# Robot_v4.net
KiCad netlist of a schematic drawn in EAGLE
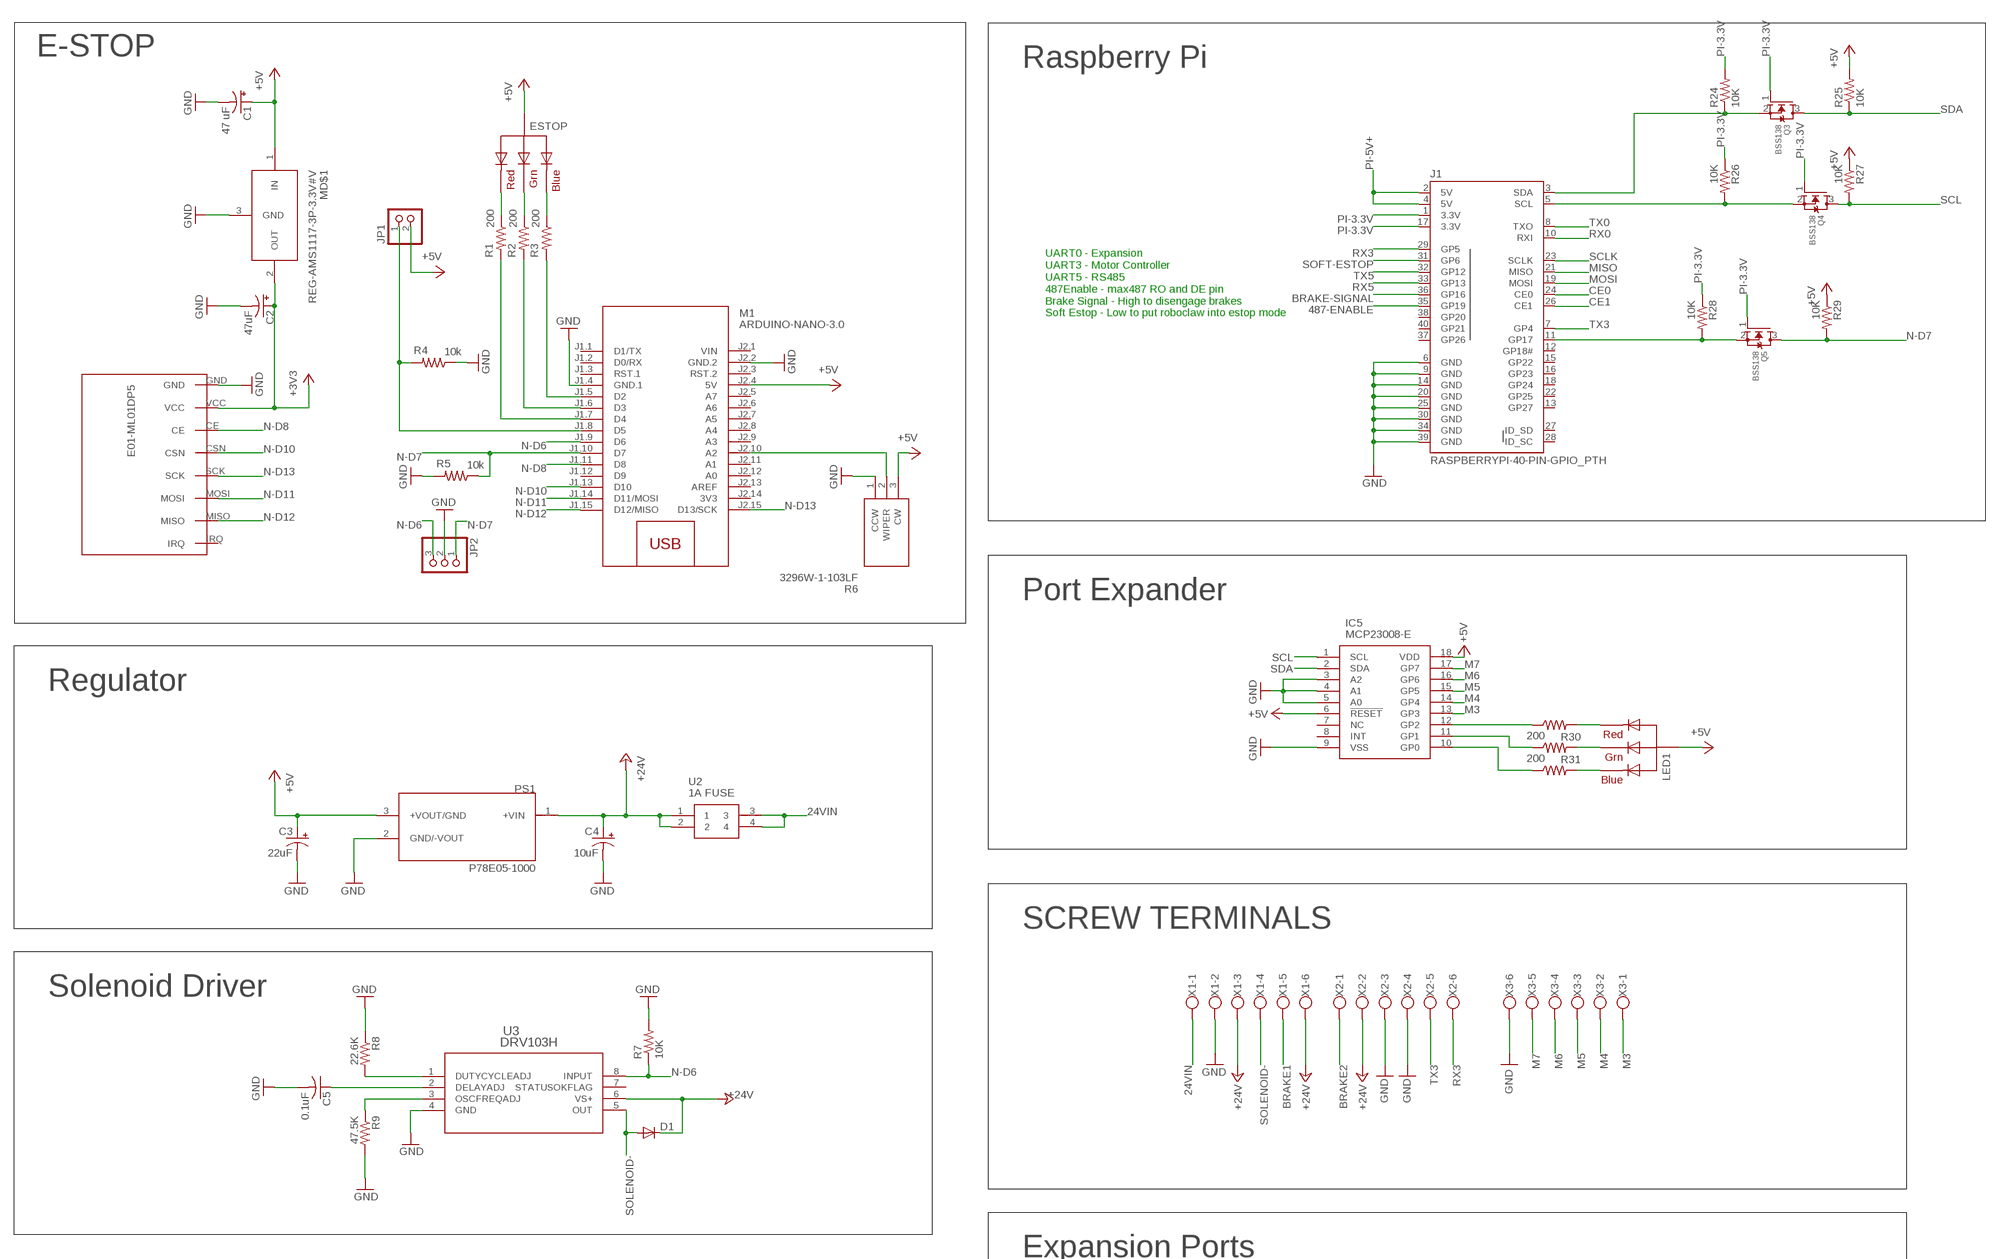
[diagram p0: schematic, sheet 1, part 1 of 2]
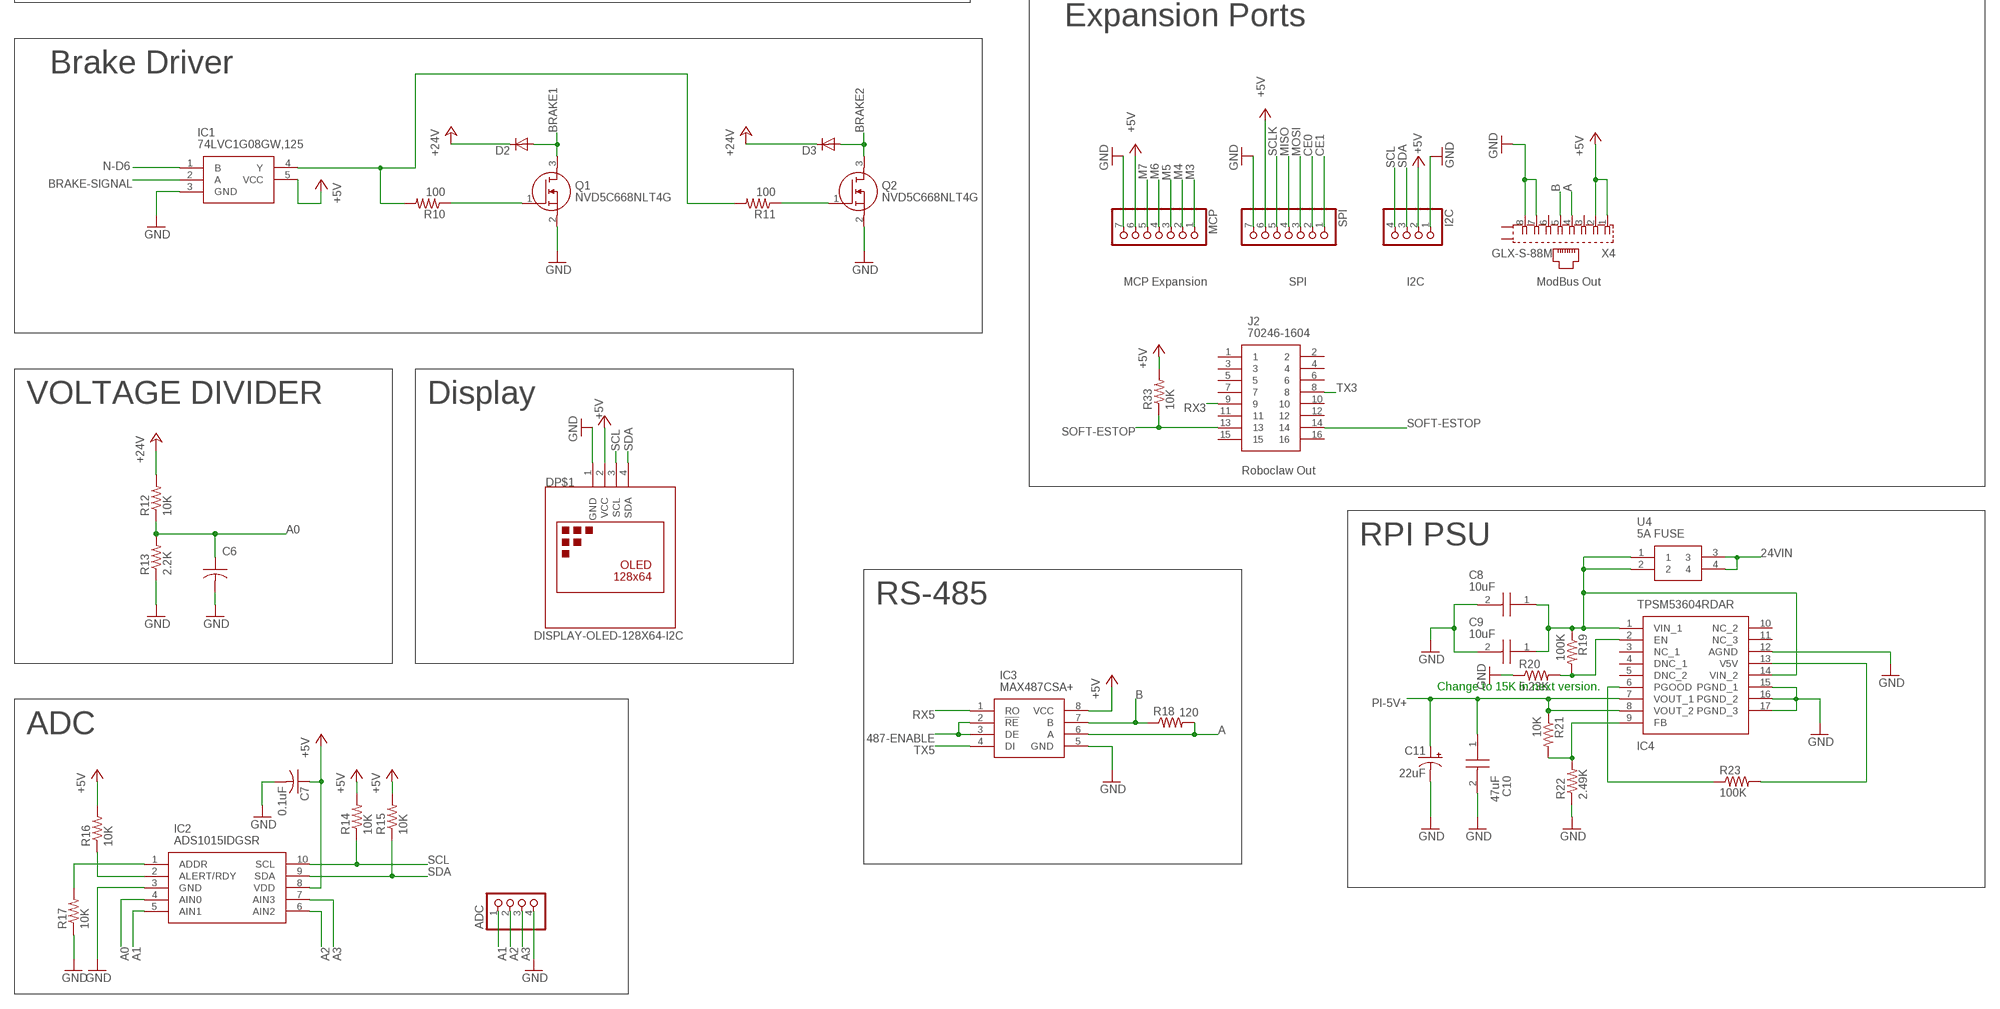
[diagram p1: schematic, sheet 1, part 2 of 2]

(export (version "E")
  (design (tool "Eeschema 10.0.6"))
  (components
    (comp (ref "ADC")
      (value "PINHD-1X4")
      (footprint "eagle-import:1X04")
      (libsource (lib "eagle-import") (part "PINHD-1X4"))
    )
    (comp (ref "C1")
      (value "47 uF")
      (footprint "eagle-import:E2,5-5")
      (libsource (lib "eagle-import") (part "CPOL-USE2.5-5"))
    )
    (comp (ref "C2")
      (value "47uF")
      (footprint "eagle-import:E2,5-5")
      (libsource (lib "eagle-import") (part "CPOL-USE2.5-5"))
    )
    (comp (ref "C3")
      (value "22uF")
      (footprint "eagle-import:E3,5-8")
      (libsource (lib "eagle-import") (part "CPOL-USE3.5-8"))
    )
    (comp (ref "C4")
      (value "10uF")
      (footprint "eagle-import:E3,5-8")
      (libsource (lib "eagle-import") (part "CPOL-USE3.5-8"))
    )
    (comp (ref "C5")
      (value "0.1uF")
      (footprint "eagle-import:C0805")
      (libsource (lib "eagle-import") (part "C-USC0805"))
    )
    (comp (ref "C6")
      (value "0.01uF")
      (footprint "eagle-import:C0805")
      (libsource (lib "eagle-import") (part "C-USC0805"))
    )
    (comp (ref "C7")
      (value "0.1uF")
      (footprint "eagle-import:C0805")
      (libsource (lib "eagle-import") (part "C-USC0805"))
    )
    (comp (ref "C8")
      (value "10uF")
      (footprint "eagle-import:CAPC3216X180N")
      (fields
        (field (name "MANUFACTURER_PART_NUMBER") "GRT31CR61H106ME01L")
        (field (name "MOUSER_PART_NUMBER") "81-GRT31CR61H106ME1L")
      )
      (libsource (lib "eagle-import") (part "GRT31CR61H106ME01L"))
    )
    (comp (ref "C9")
      (value "10uF")
      (footprint "eagle-import:CAPC3216X180N")
      (fields
        (field (name "MANUFACTURER_PART_NUMBER") "GRT31CR61H106ME01L")
        (field (name "MOUSER_PART_NUMBER") "81-GRT31CR61H106ME1L")
      )
      (libsource (lib "eagle-import") (part "GRT31CR61H106ME01L"))
    )
    (comp (ref "C10")
      (value "47uF")
      (footprint "eagle-import:CAPC2012X145N")
      (fields
        (field (name "MANUFACTURER_PART_NUMBER") "GRM21BR61A476ME15L")
        (field (name "MOUSER_PART_NUMBER") "81-GRM21BR61A476ME5L")
      )
      (libsource (lib "eagle-import") (part "GRM21BR61A476ME15L"))
    )
    (comp (ref "C11")
      (value "22uF")
      (footprint "eagle-import:E3,5-8")
      (libsource (lib "eagle-import") (part "CPOL-USE3.5-8"))
    )
    (comp (ref "D1")
      (value "DIODESOD-123")
      (footprint "eagle-import:SOD-123")
      (libsource (lib "eagle-import") (part "DIODESOD-123"))
    )
    (comp (ref "D2")
      (value "DIODESOD-123")
      (footprint "eagle-import:SOD-123")
      (libsource (lib "eagle-import") (part "DIODESOD-123"))
    )
    (comp (ref "D3")
      (value "DIODESOD-123")
      (footprint "eagle-import:SOD-123")
      (libsource (lib "eagle-import") (part "DIODESOD-123"))
    )
    (comp (ref "DP$1")
      (value "DISPLAY-OLED-128X64-I2C")
      (footprint "eagle-import:DISPLAY-OLED-128X64-I2C")
      (libsource (lib "eagle-import") (part "DISPLAY-OLED-128X64-I2C"))
    )
    (comp (ref "ESTOP")
      (value "RGBLED_CA-5MM")
      (footprint "eagle-import:LED5MMRGB")
      (libsource (lib "eagle-import") (part "RGBLED_CA-5MM"))
    )
    (comp (ref "I2C")
      (value "PINHD-1X4")
      (footprint "eagle-import:1X04")
      (libsource (lib "eagle-import") (part "PINHD-1X4"))
    )
    (comp (ref "IC1")
      (value "74LVC1G08GW,125")
      (footprint "eagle-import:SOT65P212X110-5N")
      (fields (field (name "MOUSER_PART_NUMBER") "771-74LVC1G08GW-G"))
      (libsource (lib "eagle-import") (part "74LVC1G08GW,125"))
    )
    (comp (ref "IC2")
      (value "ADS1015IDGSR")
      (footprint "eagle-import:SOP50P490X110-10N")
      (fields (field (name "MOUSER_PART_NUMBER") "595-ADS1015IDGSR"))
      (libsource (lib "eagle-import") (part "ADS1015IDGSR"))
    )
    (comp (ref "IC3")
      (value "MAX487CSA+")
      (footprint "eagle-import:SOIC127P600X175-8N")
      (fields (field (name "MOUSER_PART_NUMBER") "700-MAX487CSA"))
      (libsource (lib "eagle-import") (part "MAX487CSA+"))
    )
    (comp (ref "IC4")
      (value "TPSM53604RDAR")
      (footprint "eagle-import:TPSM53604RDAR")
      (fields (field (name "MOUSER_PART_NUMBER") "595-TPSM53604RDAR"))
      (libsource (lib "eagle-import") (part "TPSM53604RDAR"))
    )
    (comp (ref "IC5")
      (value "MCP23008-E")
      (footprint "eagle-import:SOIC127P1030X265-18N")
      (fields
        (field (name "MANUFACTURER_PART_NUMBER") "MCP23008-E/SO")
        (field (name "MOUSER_PART_NUMBER") "579-MCP23008-E/SO")
      )
      (libsource (lib "eagle-import") (part "MCP23008-E_SO"))
    )
    (comp (ref "J1")
      (value "RASPBERRYPI-40-PIN-GPIO_PTH")
      (footprint "eagle-import:2X20_SHROUDED")
      (libsource (lib "eagle-import") (part "RASPBERRYPI-40-PIN-GPIO_PTH"))
    )
    (comp (ref "J2")
      (value "70246-1604")
      (footprint "eagle-import:SHDR16W64P254_2X8_2794X889X947")
      (fields (field (name "MOUSER_PART_NUMBER") "538-70246-1604"))
      (libsource (lib "eagle-import") (part "70246-1604"))
    )
    (comp (ref "JP1")
      (value "PINHD-1X2")
      (footprint "eagle-import:1X02")
      (libsource (lib "eagle-import") (part "PINHD-1X2"))
    )
    (comp (ref "JP2")
      (value "PINHD-1X3")
      (footprint "eagle-import:1X03")
      (libsource (lib "eagle-import") (part "PINHD-1X3"))
    )
    (comp (ref "LED1")
      (value "RGBLED_CA-5MM")
      (footprint "eagle-import:LED5MMRGB")
      (libsource (lib "eagle-import") (part "RGBLED_CA-5MM"))
    )
    (comp (ref "M1")
      (value "ARDUINO-NANO-3.0")
      (footprint "eagle-import:ARDUINO-NANO-3.0")
      (libsource (lib "eagle-import") (part "ARDUINO-NANO-3.0"))
    )
    (comp (ref "MCP")
      (value "PINHD-1X7")
      (footprint "eagle-import:1X07")
      (libsource (lib "eagle-import") (part "PINHD-1X7"))
    )
    (comp (ref "MD$1")
      (value "REG-AMS1117-3P-3.3V#V")
      (footprint "eagle-import:REG-AMS1117-3P#V")
      (libsource (lib "eagle-import") (part "REG-AMS1117-3P-#V3.3V"))
    )
    (comp (ref "MD$2")
      (value "E01-ML01DP5")
      (footprint "eagle-import:E01-ML01DP5")
      (libsource (lib "eagle-import") (part "E01-ML01DP5"))
    )
    (comp (ref "PS1")
      (value "P78E05-1000")
      (footprint "eagle-import:CONV_P78E05-1000")
      (fields (field (name "MANUFACTURER") "CUI Inc"))
      (libsource (lib "eagle-import") (part "P78E05-1000"))
    )
    (comp (ref "Q1")
      (value "NVD5C668NLT4G")
      (footprint "eagle-import:DPAK_(SINGLE-GAUGE)_TO-252(369")
      (fields (field (name "MOUSER_PART_NUMBER") "863-NVD5C668NLT4G"))
      (libsource (lib "eagle-import") (part "NVD5C668NLT4G"))
    )
    (comp (ref "Q2")
      (value "NVD5C668NLT4G")
      (footprint "eagle-import:DPAK_(SINGLE-GAUGE)_TO-252(369")
      (fields (field (name "MOUSER_PART_NUMBER") "863-NVD5C668NLT4G"))
      (libsource (lib "eagle-import") (part "NVD5C668NLT4G"))
    )
    (comp (ref "Q3")
      (value "BSS138")
      (footprint "eagle-import:SOT23")
      (libsource (lib "eagle-import") (part "MOSFET-NREFLOW"))
    )
    (comp (ref "Q4")
      (value "BSS138")
      (footprint "eagle-import:SOT23")
      (libsource (lib "eagle-import") (part "MOSFET-NREFLOW"))
    )
    (comp (ref "Q5")
      (value "BSS138")
      (footprint "eagle-import:SOT23")
      (libsource (lib "eagle-import") (part "MOSFET-NREFLOW"))
    )
    (comp (ref "R1")
      (value "200")
      (footprint "eagle-import:M0805")
      (libsource (lib "eagle-import") (part "R-US_M0805"))
    )
    (comp (ref "R2")
      (value "200")
      (footprint "eagle-import:M0805")
      (libsource (lib "eagle-import") (part "R-US_M0805"))
    )
    (comp (ref "R3")
      (value "200")
      (footprint "eagle-import:M0805")
      (libsource (lib "eagle-import") (part "R-US_M0805"))
    )
    (comp (ref "R4")
      (value "10k")
      (footprint "eagle-import:M0805")
      (libsource (lib "eagle-import") (part "R-US_M0805"))
    )
    (comp (ref "R5")
      (value "10k")
      (footprint "eagle-import:M0805")
      (libsource (lib "eagle-import") (part "R-US_M0805"))
    )
    (comp (ref "R6")
      (value "3296W-1-103LF")
      (footprint "eagle-import:SHDR3W54P0X254_1X3_953X483X115")
      (fields (field (name "MOUSER_PART_NUMBER") "652-3296W-1-103LF"))
      (libsource (lib "eagle-import") (part "3296W-1-103LF"))
    )
    (comp (ref "R7")
      (value "10K")
      (footprint "eagle-import:M0805")
      (libsource (lib "eagle-import") (part "R-US_M0805"))
    )
    (comp (ref "R8")
      (value "22.6K")
      (footprint "eagle-import:M0805")
      (libsource (lib "eagle-import") (part "R-US_M0805"))
    )
    (comp (ref "R9")
      (value "47.5K")
      (footprint "eagle-import:M0805")
      (libsource (lib "eagle-import") (part "R-US_M0805"))
    )
    (comp (ref "R10")
      (value "100")
      (footprint "eagle-import:M0805")
      (libsource (lib "eagle-import") (part "R-US_M0805"))
    )
    (comp (ref "R11")
      (value "100")
      (footprint "eagle-import:M0805")
      (libsource (lib "eagle-import") (part "R-US_M0805"))
    )
    (comp (ref "R12")
      (value "10K")
      (footprint "eagle-import:M0805")
      (libsource (lib "eagle-import") (part "R-US_M0805"))
    )
    (comp (ref "R13")
      (value "2.2K")
      (footprint "eagle-import:M0805")
      (libsource (lib "eagle-import") (part "R-US_M0805"))
    )
    (comp (ref "R14")
      (value "10K")
      (footprint "eagle-import:R0805")
      (libsource (lib "eagle-import") (part "R-US_R0805"))
    )
    (comp (ref "R15")
      (value "10K")
      (footprint "eagle-import:R0805")
      (libsource (lib "eagle-import") (part "R-US_R0805"))
    )
    (comp (ref "R16")
      (value "10K")
      (footprint "eagle-import:R0805")
      (libsource (lib "eagle-import") (part "R-US_R0805"))
    )
    (comp (ref "R17")
      (value "10K")
      (footprint "eagle-import:R0805")
      (libsource (lib "eagle-import") (part "R-US_R0805"))
    )
    (comp (ref "R18")
      (value "120")
      (footprint "eagle-import:R0805")
      (libsource (lib "eagle-import") (part "R-US_R0805"))
    )
    (comp (ref "R19")
      (value "100K")
      (footprint "eagle-import:R0805")
      (libsource (lib "eagle-import") (part "R-US_R0805"))
    )
    (comp (ref "R20")
      (value "5.23K")
      (footprint "eagle-import:R0805")
      (libsource (lib "eagle-import") (part "R-US_R0805"))
    )
    (comp (ref "R21")
      (value "10K")
      (footprint "eagle-import:R0805")
      (libsource (lib "eagle-import") (part "R-US_R0805"))
    )
    (comp (ref "R22")
      (value "2.49K")
      (footprint "eagle-import:R0805")
      (libsource (lib "eagle-import") (part "R-US_R0805"))
    )
    (comp (ref "R23")
      (value "100K")
      (footprint "eagle-import:R0805")
      (libsource (lib "eagle-import") (part "R-US_R0805"))
    )
    (comp (ref "R24")
      (value "10K")
      (footprint "eagle-import:R0805")
      (libsource (lib "eagle-import") (part "R-US_R0805"))
    )
    (comp (ref "R25")
      (value "10K")
      (footprint "eagle-import:R0805")
      (libsource (lib "eagle-import") (part "R-US_R0805"))
    )
    (comp (ref "R26")
      (value "10K")
      (footprint "eagle-import:R0805")
      (libsource (lib "eagle-import") (part "R-US_R0805"))
    )
    (comp (ref "R27")
      (value "10K")
      (footprint "eagle-import:R0805")
      (libsource (lib "eagle-import") (part "R-US_R0805"))
    )
    (comp (ref "R28")
      (value "10K")
      (footprint "eagle-import:R0805")
      (libsource (lib "eagle-import") (part "R-US_R0805"))
    )
    (comp (ref "R29")
      (value "10K")
      (footprint "eagle-import:R0805")
      (libsource (lib "eagle-import") (part "R-US_R0805"))
    )
    (comp (ref "R30")
      (value "200")
      (footprint "eagle-import:M0805")
      (libsource (lib "eagle-import") (part "R-US_M0805"))
    )
    (comp (ref "R31")
      (value "200")
      (footprint "eagle-import:M0805")
      (libsource (lib "eagle-import") (part "R-US_M0805"))
    )
    (comp (ref "R32")
      (value "200")
      (footprint "eagle-import:M0805")
      (libsource (lib "eagle-import") (part "R-US_M0805"))
    )
    (comp (ref "R33")
      (value "10K")
      (footprint "eagle-import:R0805")
      (libsource (lib "eagle-import") (part "R-US_R0805"))
    )
    (comp (ref "SPI")
      (value "PINHD-1X7")
      (footprint "eagle-import:1X07")
      (libsource (lib "eagle-import") (part "PINHD-1X7"))
    )
    (comp (ref "U2")
      (value "1A FUSE")
      (footprint "eagle-import:3568")
      (fields (field (name "MANUFACTURER_PART_NUMBER") "3568") (field (name "MOUSER_PART_NUMBER") "534-3568"))
      (libsource (lib "eagle-import") (part "3568"))
    )
    (comp (ref "U3")
      (value "DRV103H")
      (footprint "eagle-import:DDA8")
      (libsource (lib "eagle-import") (part "DRV103H"))
    )
    (comp (ref "U4")
      (value "5A FUSE")
      (footprint "eagle-import:3568")
      (fields (field (name "MANUFACTURER_PART_NUMBER") "3568") (field (name "MOUSER_PART_NUMBER") "534-3568"))
      (libsource (lib "eagle-import") (part "3568"))
    )
    (comp (ref "X1")
      (value "W237-136")
      (footprint "eagle-import:W237-136")
      (fields (field (name "MPN") "237-136"))
      (libsource (lib "eagle-import") (part "W237-136"))
    )
    (comp (ref "X2")
      (value "W237-136")
      (footprint "eagle-import:W237-136")
      (fields (field (name "MPN") "237-136"))
      (libsource (lib "eagle-import") (part "W237-136"))
    )
    (comp (ref "X3")
      (value "W237-136")
      (footprint "eagle-import:W237-136")
      (fields (field (name "MPN") "237-136"))
      (libsource (lib "eagle-import") (part "W237-136"))
    )
    (comp (ref "X4")
      (value "GLX-S-88M")
      (footprint "eagle-import:GLX-S-88M")
      (libsource (lib "eagle-import") (part "GLX-S-88M"))
    )
  )
  (nets
    (net (code "1") (name "+3V3") (class "Default")
      (node (ref "C2") (pin "+") (pinfunction "+_+") (pintype "passive"))
      (node (ref "MD$1") (pin "2") (pinfunction "OUT_2") (pintype "bidirectional"))
      (node (ref "MD$2") (pin "VCC") (pinfunction "VCC_VCC") (pintype "bidirectional"))
    )
    (net (code "2") (name "+5V") (class "Default")
      (node (ref "C1") (pin "+") (pinfunction "+_+") (pintype "passive"))
      (node (ref "C3") (pin "+") (pinfunction "+_+") (pintype "passive"))
      (node (ref "C7") (pin "1") (pinfunction "1_1") (pintype "passive"))
      (node (ref "DP$1") (pin "2") (pinfunction "VCC_2") (pintype "power_in"))
      (node (ref "ESTOP") (pin "2") (pinfunction "VCC_2") (pintype "bidirectional"))
      (node (ref "I2C") (pin "2") (pinfunction "2_2") (pintype "passive"))
      (node (ref "IC1") (pin "5") (pinfunction "VCC_5") (pintype "power_in"))
      (node (ref "IC2") (pin "8") (pinfunction "VDD_8") (pintype "bidirectional"))
      (node (ref "IC3") (pin "8") (pinfunction "VCC_8") (pintype "power_in"))
      (node (ref "IC5") (pin "18") (pinfunction "VDD_18") (pintype "power_in"))
      (node (ref "IC5") (pin "6") (pinfunction "~{RESET}_6") (pintype "bidirectional"))
      (node (ref "JP1") (pin "2") (pinfunction "2_2") (pintype "passive"))
      (node (ref "LED1") (pin "2") (pinfunction "VCC_2") (pintype "bidirectional"))
      (node (ref "M1") (pin "J2.4") (pinfunction "5V_J2.4") (pintype "power_in"))
      (node (ref "MCP") (pin "6") (pinfunction "6_6") (pintype "passive"))
      (node (ref "MD$1") (pin "1") (pinfunction "IN_1") (pintype "bidirectional"))
      (node (ref "PS1") (pin "3") (pinfunction "+VOUT/GND_3") (pintype "power_in"))
      (node (ref "R14") (pin "2") (pinfunction "2_2") (pintype "passive"))
      (node (ref "R15") (pin "2") (pinfunction "2_2") (pintype "passive"))
      (node (ref "R16") (pin "2") (pinfunction "2_2") (pintype "passive"))
      (node (ref "R25") (pin "2") (pinfunction "2_2") (pintype "passive"))
      (node (ref "R27") (pin "1") (pinfunction "1_1") (pintype "passive"))
      (node (ref "R29") (pin "1") (pinfunction "1_1") (pintype "passive"))
      (node (ref "R33") (pin "2") (pinfunction "2_2") (pintype "passive"))
      (node (ref "R6") (pin "3") (pinfunction "CW_3") (pintype "bidirectional"))
      (node (ref "SPI") (pin "6") (pinfunction "6_6") (pintype "passive"))
      (node (ref "X4") (pin "1") (pinfunction "1_1") (pintype "passive"))
      (node (ref "X4") (pin "2") (pinfunction "2_2") (pintype "passive"))
    )
    (net (code "3") (name "+24V") (class "Default")
      (node (ref "C4") (pin "+") (pinfunction "+_+") (pintype "passive"))
      (node (ref "D1") (pin "C") (pinfunction "C_C") (pintype "passive"))
      (node (ref "D2") (pin "C") (pinfunction "C_C") (pintype "passive"))
      (node (ref "D3") (pin "C") (pinfunction "C_C") (pintype "passive"))
      (node (ref "PS1") (pin "1") (pinfunction "+VIN_1") (pintype "input"))
      (node (ref "R12") (pin "2") (pinfunction "2_2") (pintype "passive"))
      (node (ref "U2") (pin "1") (pinfunction "1_1") (pintype "bidirectional"))
      (node (ref "U2") (pin "2") (pinfunction "2_2") (pintype "bidirectional"))
      (node (ref "U3") (pin "6") (pinfunction "VS+_6") (pintype "power_in"))
      (node (ref "X1") (pin "3") (pinfunction "KL_3") (pintype "passive"))
      (node (ref "X1") (pin "6") (pinfunction "KL_6") (pintype "passive"))
      (node (ref "X2") (pin "2") (pinfunction "KL_2") (pintype "passive"))
    )
    (net (code "4") (name "/3V3") (class "Default")
      (node (ref "M1") (pin "J2.14") (pinfunction "3V3_J2.14") (pintype "power_in"))
    )
    (net (code "5") (name "/24VIN") (class "Default")
      (node (ref "U2") (pin "3") (pinfunction "3_3") (pintype "bidirectional"))
      (node (ref "U2") (pin "4") (pinfunction "4_4") (pintype "bidirectional"))
      (node (ref "U4") (pin "3") (pinfunction "3_3") (pintype "bidirectional"))
      (node (ref "U4") (pin "4") (pinfunction "4_4") (pintype "bidirectional"))
      (node (ref "X1") (pin "1") (pinfunction "KL_1") (pintype "passive"))
    )
    (net (code "6") (name "/487-ENABLE") (class "Default")
      (node (ref "IC3") (pin "2") (pinfunction "~{RE}_2") (pintype "bidirectional"))
      (node (ref "IC3") (pin "3") (pinfunction "DE_3") (pintype "bidirectional"))
      (node (ref "J1") (pin "35") (pinfunction "GP19_35") (pintype "bidirectional"))
    )
    (net (code "7") (name "/A") (class "Default")
      (node (ref "IC3") (pin "6") (pinfunction "A_6") (pintype "bidirectional"))
      (node (ref "R18") (pin "2") (pinfunction "2_2") (pintype "passive"))
      (node (ref "X4") (pin "4") (pinfunction "4_4") (pintype "passive"))
    )
    (net (code "8") (name "/A0") (class "Default")
      (node (ref "C6") (pin "1") (pinfunction "1_1") (pintype "passive"))
      (node (ref "IC2") (pin "4") (pinfunction "AIN0_4") (pintype "bidirectional"))
      (node (ref "R12") (pin "1") (pinfunction "1_1") (pintype "passive"))
      (node (ref "R13") (pin "2") (pinfunction "2_2") (pintype "passive"))
    )
    (net (code "9") (name "/A1") (class "Default")
      (node (ref "ADC") (pin "1") (pinfunction "1_1") (pintype "passive"))
      (node (ref "IC2") (pin "5") (pinfunction "AIN1_5") (pintype "bidirectional"))
    )
    (net (code "10") (name "/A2") (class "Default")
      (node (ref "ADC") (pin "2") (pinfunction "2_2") (pintype "passive"))
      (node (ref "IC2") (pin "6") (pinfunction "AIN2_6") (pintype "bidirectional"))
    )
    (net (code "11") (name "/A3") (class "Default")
      (node (ref "ADC") (pin "3") (pinfunction "3_3") (pintype "passive"))
      (node (ref "IC2") (pin "7") (pinfunction "AIN3_7") (pintype "bidirectional"))
    )
    (net (code "12") (name "/B") (class "Default")
      (node (ref "IC3") (pin "7") (pinfunction "B_7") (pintype "bidirectional"))
      (node (ref "R18") (pin "1") (pinfunction "1_1") (pintype "passive"))
      (node (ref "X4") (pin "5") (pinfunction "5_5") (pintype "passive"))
    )
    (net (code "13") (name "/BRAKE-SIGNAL") (class "Default")
      (node (ref "IC1") (pin "2") (pinfunction "A_2") (pintype "bidirectional"))
      (node (ref "J1") (pin "36") (pinfunction "GP16_36") (pintype "bidirectional"))
    )
    (net (code "14") (name "/BRAKE1") (class "Default")
      (node (ref "D2") (pin "A") (pinfunction "A_A") (pintype "passive"))
      (node (ref "Q1") (pin "3") (pinfunction "D_3") (pintype "bidirectional"))
      (node (ref "X1") (pin "5") (pinfunction "KL_5") (pintype "passive"))
    )
    (net (code "15") (name "/BRAKE2") (class "Default")
      (node (ref "D3") (pin "A") (pinfunction "A_A") (pintype "passive"))
      (node (ref "Q2") (pin "3") (pinfunction "D_3") (pintype "bidirectional"))
      (node (ref "X2") (pin "1") (pinfunction "KL_1") (pintype "passive"))
    )
    (net (code "16") (name "/CE0") (class "Default")
      (node (ref "J1") (pin "24") (pinfunction "CE0_24") (pintype "output"))
      (node (ref "SPI") (pin "2") (pinfunction "2_2") (pintype "passive"))
    )
    (net (code "17") (name "/CE1") (class "Default")
      (node (ref "J1") (pin "26") (pinfunction "CE1_26") (pintype "output"))
      (node (ref "SPI") (pin "1") (pinfunction "1_1") (pintype "passive"))
    )
    (net (code "18") (name "/M3") (class "Default")
      (node (ref "IC5") (pin "13") (pinfunction "GP3_13") (pintype "bidirectional"))
      (node (ref "MCP") (pin "1") (pinfunction "1_1") (pintype "passive"))
      (node (ref "X3") (pin "1") (pinfunction "KL_1") (pintype "passive"))
    )
    (net (code "19") (name "/M4") (class "Default")
      (node (ref "IC5") (pin "14") (pinfunction "GP4_14") (pintype "bidirectional"))
      (node (ref "MCP") (pin "2") (pinfunction "2_2") (pintype "passive"))
      (node (ref "X3") (pin "2") (pinfunction "KL_2") (pintype "passive"))
    )
    (net (code "20") (name "/M5") (class "Default")
      (node (ref "IC5") (pin "15") (pinfunction "GP5_15") (pintype "bidirectional"))
      (node (ref "MCP") (pin "3") (pinfunction "3_3") (pintype "passive"))
      (node (ref "X3") (pin "3") (pinfunction "KL_3") (pintype "passive"))
    )
    (net (code "21") (name "/M6") (class "Default")
      (node (ref "IC5") (pin "16") (pinfunction "GP6_16") (pintype "bidirectional"))
      (node (ref "MCP") (pin "4") (pinfunction "4_4") (pintype "passive"))
      (node (ref "X3") (pin "4") (pinfunction "KL_4") (pintype "passive"))
    )
    (net (code "22") (name "/M7") (class "Default")
      (node (ref "IC5") (pin "17") (pinfunction "GP7_17") (pintype "bidirectional"))
      (node (ref "MCP") (pin "5") (pinfunction "5_5") (pintype "passive"))
      (node (ref "X3") (pin "5") (pinfunction "KL_5") (pintype "passive"))
    )
    (net (code "23") (name "/MISO") (class "Default")
      (node (ref "J1") (pin "21") (pinfunction "MISO_21") (pintype "input"))
      (node (ref "SPI") (pin "4") (pinfunction "4_4") (pintype "passive"))
    )
    (net (code "24") (name "/MOSI") (class "Default")
      (node (ref "J1") (pin "19") (pinfunction "MOSI_19") (pintype "output"))
      (node (ref "SPI") (pin "3") (pinfunction "3_3") (pintype "passive"))
    )
    (net (code "25") (name "/N-D6") (class "Default")
      (node (ref "IC1") (pin "1") (pinfunction "B_1") (pintype "bidirectional"))
      (node (ref "JP2") (pin "3") (pinfunction "3_3") (pintype "passive"))
      (node (ref "M1") (pin "J1.9") (pinfunction "D6_J1.9") (pintype "bidirectional"))
      (node (ref "R7") (pin "1") (pinfunction "1_1") (pintype "passive"))
      (node (ref "U3") (pin "8") (pinfunction "INPUT_8") (pintype "input"))
    )
    (net (code "26") (name "/N-D7") (class "Default")
      (node (ref "JP2") (pin "1") (pinfunction "1_1") (pintype "passive"))
      (node (ref "M1") (pin "J1.10") (pinfunction "D7_J1.10") (pintype "bidirectional"))
      (node (ref "Q5") (pin "3") (pinfunction "D_3") (pintype "bidirectional"))
      (node (ref "R29") (pin "2") (pinfunction "2_2") (pintype "passive"))
      (node (ref "R5") (pin "1") (pinfunction "1_1") (pintype "passive"))
    )
    (net (code "27") (name "/N-D8") (class "Default")
      (node (ref "M1") (pin "J1.11") (pinfunction "D8_J1.11") (pintype "bidirectional"))
      (node (ref "MD$2") (pin "CE") (pinfunction "CE_CE") (pintype "bidirectional"))
    )
    (net (code "28") (name "/N-D10") (class "Default")
      (node (ref "M1") (pin "J1.13") (pinfunction "D10_J1.13") (pintype "bidirectional"))
      (node (ref "MD$2") (pin "CSN") (pinfunction "CSN_CSN") (pintype "bidirectional"))
    )
    (net (code "29") (name "/N-D11") (class "Default")
      (node (ref "M1") (pin "J1.14") (pinfunction "D11/MOSI_J1.14") (pintype "bidirectional"))
      (node (ref "MD$2") (pin "MOSI") (pinfunction "MOSI_MOSI") (pintype "bidirectional"))
    )
    (net (code "30") (name "/N-D12") (class "Default")
      (node (ref "M1") (pin "J1.15") (pinfunction "D12/MISO_J1.15") (pintype "bidirectional"))
      (node (ref "MD$2") (pin "MISO") (pinfunction "MISO_MISO") (pintype "bidirectional"))
    )
    (net (code "31") (name "/N-D13") (class "Default")
      (node (ref "M1") (pin "J2.15") (pinfunction "D13/SCK_J2.15") (pintype "bidirectional"))
      (node (ref "MD$2") (pin "SCK") (pinfunction "SCK_SCK") (pintype "bidirectional"))
    )
    (net (code "32") (name "/PI-3.3V") (class "Default")
      (node (ref "J1") (pin "1") (pinfunction "3.3V_1") (pintype "power_in"))
      (node (ref "J1") (pin "17") (pinfunction "3.3V_17") (pintype "power_in"))
      (node (ref "Q3") (pin "1") (pinfunction "G_1") (pintype "bidirectional"))
      (node (ref "Q4") (pin "1") (pinfunction "G_1") (pintype "bidirectional"))
      (node (ref "Q5") (pin "1") (pinfunction "G_1") (pintype "bidirectional"))
      (node (ref "R24") (pin "2") (pinfunction "2_2") (pintype "passive"))
      (node (ref "R26") (pin "1") (pinfunction "1_1") (pintype "passive"))
      (node (ref "R28") (pin "1") (pinfunction "1_1") (pintype "passive"))
    )
    (net (code "33") (name "/PI-5V+") (class "Default")
      (node (ref "C10") (pin "1") (pinfunction "1_1") (pintype "bidirectional"))
      (node (ref "C11") (pin "+") (pinfunction "+_+") (pintype "passive"))
      (node (ref "IC4") (pin "7") (pinfunction "VOUT_1_7") (pintype "bidirectional"))
      (node (ref "IC4") (pin "8") (pinfunction "VOUT_2_8") (pintype "bidirectional"))
      (node (ref "J1") (pin "2") (pinfunction "5V_2") (pintype "power_in"))
      (node (ref "J1") (pin "4") (pinfunction "5V_4") (pintype "power_in"))
      (node (ref "R21") (pin "1") (pinfunction "1_1") (pintype "passive"))
    )
    (net (code "34") (name "/RX0") (class "Default")
      (node (ref "J1") (pin "10") (pinfunction "RXI_10") (pintype "input"))
    )
    (net (code "35") (name "/RX3") (class "Default")
      (node (ref "J1") (pin "29") (pinfunction "GP5_29") (pintype "bidirectional"))
      (node (ref "J2") (pin "9") (pinfunction "9_9") (pintype "bidirectional"))
      (node (ref "X2") (pin "6") (pinfunction "KL_6") (pintype "passive"))
    )
    (net (code "36") (name "/RX5") (class "Default")
      (node (ref "IC3") (pin "1") (pinfunction "RO_1") (pintype "bidirectional"))
      (node (ref "J1") (pin "33") (pinfunction "GP13_33") (pintype "bidirectional"))
    )
    (net (code "37") (name "/SCL") (class "Default")
      (node (ref "DP$1") (pin "3") (pinfunction "SCL_3") (pintype "bidirectional"))
      (node (ref "I2C") (pin "4") (pinfunction "4_4") (pintype "passive"))
      (node (ref "IC2") (pin "10") (pinfunction "SCL_10") (pintype "bidirectional"))
      (node (ref "IC5") (pin "1") (pinfunction "SCL_1") (pintype "bidirectional"))
      (node (ref "Q4") (pin "3") (pinfunction "D_3") (pintype "bidirectional"))
      (node (ref "R14") (pin "1") (pinfunction "1_1") (pintype "passive"))
      (node (ref "R27") (pin "2") (pinfunction "2_2") (pintype "passive"))
    )
    (net (code "38") (name "/SCLK") (class "Default")
      (node (ref "J1") (pin "23") (pinfunction "SCLK_23") (pintype "output"))
      (node (ref "SPI") (pin "5") (pinfunction "5_5") (pintype "passive"))
    )
    (net (code "39") (name "/SDA") (class "Default")
      (node (ref "DP$1") (pin "4") (pinfunction "SDA_4") (pintype "bidirectional"))
      (node (ref "I2C") (pin "3") (pinfunction "3_3") (pintype "passive"))
      (node (ref "IC2") (pin "9") (pinfunction "SDA_9") (pintype "bidirectional"))
      (node (ref "IC5") (pin "2") (pinfunction "SDA_2") (pintype "bidirectional"))
      (node (ref "Q3") (pin "3") (pinfunction "D_3") (pintype "bidirectional"))
      (node (ref "R15") (pin "1") (pinfunction "1_1") (pintype "passive"))
      (node (ref "R25") (pin "1") (pinfunction "1_1") (pintype "passive"))
    )
    (net (code "40") (name "/SOFT-ESTOP") (class "Default")
      (node (ref "J1") (pin "31") (pinfunction "GP6_31") (pintype "bidirectional"))
      (node (ref "J2") (pin "13") (pinfunction "13_13") (pintype "bidirectional"))
      (node (ref "J2") (pin "14") (pinfunction "14_14") (pintype "bidirectional"))
      (node (ref "R33") (pin "1") (pinfunction "1_1") (pintype "passive"))
    )
    (net (code "41") (name "/SOLENOID-") (class "Default")
      (node (ref "D1") (pin "A") (pinfunction "A_A") (pintype "passive"))
      (node (ref "U3") (pin "5") (pinfunction "OUT_5") (pintype "output"))
      (node (ref "X1") (pin "4") (pinfunction "KL_4") (pintype "passive"))
    )
    (net (code "42") (name "/TX0") (class "Default")
      (node (ref "J1") (pin "8") (pinfunction "TXO_8") (pintype "output"))
    )
    (net (code "43") (name "/TX3") (class "Default")
      (node (ref "J1") (pin "7") (pinfunction "GP4_7") (pintype "bidirectional"))
      (node (ref "J2") (pin "8") (pinfunction "8_8") (pintype "bidirectional"))
      (node (ref "X2") (pin "5") (pinfunction "KL_5") (pintype "passive"))
    )
    (net (code "44") (name "/TX5") (class "Default")
      (node (ref "IC3") (pin "4") (pinfunction "DI_4") (pintype "bidirectional"))
      (node (ref "J1") (pin "32") (pinfunction "GP12_32") (pintype "bidirectional"))
    )
    (net (code "45") (name "/VIN") (class "Default")
      (node (ref "M1") (pin "J2.1") (pinfunction "VIN_J2.1") (pintype "power_in"))
    )
    (net (code "46") (name "GND") (class "Default")
      (node (ref "ADC") (pin "4") (pinfunction "4_4") (pintype "passive"))
      (node (ref "C1") (pin "-") (pinfunction "-_-") (pintype "passive"))
      (node (ref "C10") (pin "2") (pinfunction "2_2") (pintype "bidirectional"))
      (node (ref "C11") (pin "-") (pinfunction "-_-") (pintype "passive"))
      (node (ref "C2") (pin "-") (pinfunction "-_-") (pintype "passive"))
      (node (ref "C3") (pin "-") (pinfunction "-_-") (pintype "passive"))
      (node (ref "C4") (pin "-") (pinfunction "-_-") (pintype "passive"))
      (node (ref "C5") (pin "2") (pinfunction "2_2") (pintype "passive"))
      (node (ref "C6") (pin "2") (pinfunction "2_2") (pintype "passive"))
      (node (ref "C7") (pin "2") (pinfunction "2_2") (pintype "passive"))
      (node (ref "C8") (pin "2") (pinfunction "2_2") (pintype "bidirectional"))
      (node (ref "C9") (pin "2") (pinfunction "2_2") (pintype "bidirectional"))
      (node (ref "DP$1") (pin "1") (pinfunction "GND_1") (pintype "power_in"))
      (node (ref "I2C") (pin "1") (pinfunction "1_1") (pintype "passive"))
      (node (ref "IC1") (pin "3") (pinfunction "GND_3") (pintype "power_in"))
      (node (ref "IC2") (pin "3") (pinfunction "GND_3") (pintype "bidirectional"))
      (node (ref "IC3") (pin "5") (pinfunction "GND_5") (pintype "power_in"))
      (node (ref "IC4") (pin "12") (pinfunction "AGND_12") (pintype "bidirectional"))
      (node (ref "IC4") (pin "15") (pinfunction "PGND_1_15") (pintype "bidirectional"))
      (node (ref "IC4") (pin "16") (pinfunction "PGND_2_16") (pintype "bidirectional"))
      (node (ref "IC4") (pin "17") (pinfunction "PGND_3_17") (pintype "bidirectional"))
      (node (ref "IC5") (pin "3") (pinfunction "A2_3") (pintype "bidirectional"))
      (node (ref "IC5") (pin "4") (pinfunction "A1_4") (pintype "bidirectional"))
      (node (ref "IC5") (pin "5") (pinfunction "A0_5") (pintype "bidirectional"))
      (node (ref "IC5") (pin "9") (pinfunction "VSS_9") (pintype "power_in"))
      (node (ref "J1") (pin "14") (pinfunction "GND_14") (pintype "power_in"))
      (node (ref "J1") (pin "20") (pinfunction "GND_20") (pintype "power_in"))
      (node (ref "J1") (pin "25") (pinfunction "GND_25") (pintype "power_in"))
      (node (ref "J1") (pin "30") (pinfunction "GND_30") (pintype "power_in"))
      (node (ref "J1") (pin "34") (pinfunction "GND_34") (pintype "power_in"))
      (node (ref "J1") (pin "39") (pinfunction "GND_39") (pintype "power_in"))
      (node (ref "J1") (pin "6") (pinfunction "GND_6") (pintype "power_in"))
      (node (ref "J1") (pin "9") (pinfunction "GND_9") (pintype "power_in"))
      (node (ref "JP2") (pin "2") (pinfunction "2_2") (pintype "passive"))
      (node (ref "M1") (pin "J1.4") (pinfunction "GND.1_J1.4") (pintype "power_in"))
      (node (ref "M1") (pin "J2.2") (pinfunction "GND.2_J2.2") (pintype "power_in"))
      (node (ref "MCP") (pin "7") (pinfunction "7_7") (pintype "passive"))
      (node (ref "MD$1") (pin "3") (pinfunction "GND_3") (pintype "bidirectional"))
      (node (ref "MD$2") (pin "GND") (pinfunction "GND_GND") (pintype "bidirectional"))
      (node (ref "PS1") (pin "2") (pinfunction "GND/-VOUT_2") (pintype "power_in"))
      (node (ref "Q1") (pin "2") (pinfunction "S_2") (pintype "bidirectional"))
      (node (ref "Q2") (pin "2") (pinfunction "S_2") (pintype "bidirectional"))
      (node (ref "R13") (pin "1") (pinfunction "1_1") (pintype "passive"))
      (node (ref "R17") (pin "1") (pinfunction "1_1") (pintype "passive"))
      (node (ref "R20") (pin "1") (pinfunction "1_1") (pintype "passive"))
      (node (ref "R22") (pin "1") (pinfunction "1_1") (pintype "passive"))
      (node (ref "R4") (pin "1") (pinfunction "1_1") (pintype "passive"))
      (node (ref "R5") (pin "2") (pinfunction "2_2") (pintype "passive"))
      (node (ref "R6") (pin "1") (pinfunction "CCW_1") (pintype "bidirectional"))
      (node (ref "R7") (pin "2") (pinfunction "2_2") (pintype "passive"))
      (node (ref "R8") (pin "1") (pinfunction "1_1") (pintype "passive"))
      (node (ref "R9") (pin "2") (pinfunction "2_2") (pintype "passive"))
      (node (ref "SPI") (pin "7") (pinfunction "7_7") (pintype "passive"))
      (node (ref "U3") (pin "4") (pinfunction "GND_4") (pintype "power_in"))
      (node (ref "X1") (pin "2") (pinfunction "KL_2") (pintype "passive"))
      (node (ref "X2") (pin "3") (pinfunction "KL_3") (pintype "passive"))
      (node (ref "X2") (pin "4") (pinfunction "KL_4") (pintype "passive"))
      (node (ref "X3") (pin "6") (pinfunction "KL_6") (pintype "passive"))
      (node (ref "X4") (pin "7") (pinfunction "7_7") (pintype "passive"))
      (node (ref "X4") (pin "8") (pinfunction "8_8") (pintype "passive"))
    )
    (net (code "47") (name "Net-(ESTOP-BLUE)") (class "Default")
      (node (ref "ESTOP") (pin "4") (pinfunction "BLUE_4") (pintype "bidirectional"))
      (node (ref "R3") (pin "1") (pinfunction "1_1") (pintype "passive"))
    )
    (net (code "48") (name "Net-(ESTOP-GREEN)") (class "Default")
      (node (ref "ESTOP") (pin "3") (pinfunction "GREEN_3") (pintype "bidirectional"))
      (node (ref "R2") (pin "1") (pinfunction "1_1") (pintype "passive"))
    )
    (net (code "49") (name "Net-(ESTOP-RED)") (class "Default")
      (node (ref "ESTOP") (pin "1") (pinfunction "RED_1") (pintype "bidirectional"))
      (node (ref "R1") (pin "1") (pinfunction "1_1") (pintype "passive"))
    )
    (net (code "50") (name "Net-(IC1-Y)") (class "Default")
      (node (ref "IC1") (pin "4") (pinfunction "Y_4") (pintype "bidirectional"))
      (node (ref "R10") (pin "2") (pinfunction "2_2") (pintype "passive"))
      (node (ref "R11") (pin "2") (pinfunction "2_2") (pintype "passive"))
    )
    (net (code "51") (name "Net-(IC2-ADDR)") (class "Default")
      (node (ref "IC2") (pin "1") (pinfunction "ADDR_1") (pintype "bidirectional"))
      (node (ref "R17") (pin "2") (pinfunction "2_2") (pintype "passive"))
    )
    (net (code "52") (name "Net-(IC2-ALERT{slash}RDY)") (class "Default")
      (node (ref "IC2") (pin "2") (pinfunction "ALERT/RDY_2") (pintype "bidirectional"))
      (node (ref "R16") (pin "1") (pinfunction "1_1") (pintype "passive"))
    )
    (net (code "53") (name "Net-(IC4-EN)") (class "Default")
      (node (ref "IC4") (pin "2") (pinfunction "EN_2") (pintype "bidirectional"))
      (node (ref "R19") (pin "2") (pinfunction "2_2") (pintype "passive"))
      (node (ref "R20") (pin "2") (pinfunction "2_2") (pintype "passive"))
    )
    (net (code "54") (name "Net-(IC4-FB)") (class "Default")
      (node (ref "IC4") (pin "9") (pinfunction "FB_9") (pintype "bidirectional"))
      (node (ref "R21") (pin "2") (pinfunction "2_2") (pintype "passive"))
      (node (ref "R22") (pin "2") (pinfunction "2_2") (pintype "passive"))
    )
    (net (code "55") (name "Net-(IC4-PGOOD)") (class "Default")
      (node (ref "IC4") (pin "6") (pinfunction "PGOOD_6") (pintype "bidirectional"))
      (node (ref "R23") (pin "1") (pinfunction "1_1") (pintype "passive"))
    )
    (net (code "56") (name "Net-(IC4-V5V)") (class "Default")
      (node (ref "IC4") (pin "13") (pinfunction "V5V_13") (pintype "bidirectional"))
      (node (ref "R23") (pin "2") (pinfunction "2_2") (pintype "passive"))
    )
    (net (code "57") (name "Net-(IC4-VIN_1)") (class "Default")
      (node (ref "C8") (pin "1") (pinfunction "1_1") (pintype "bidirectional"))
      (node (ref "C9") (pin "1") (pinfunction "1_1") (pintype "bidirectional"))
      (node (ref "IC4") (pin "1") (pinfunction "VIN_1_1") (pintype "bidirectional"))
      (node (ref "IC4") (pin "14") (pinfunction "VIN_2_14") (pintype "bidirectional"))
      (node (ref "R19") (pin "1") (pinfunction "1_1") (pintype "passive"))
      (node (ref "U4") (pin "1") (pinfunction "1_1") (pintype "bidirectional"))
      (node (ref "U4") (pin "2") (pinfunction "2_2") (pintype "bidirectional"))
    )
    (net (code "58") (name "Net-(IC5-GP0)") (class "Default")
      (node (ref "IC5") (pin "10") (pinfunction "GP0_10") (pintype "bidirectional"))
      (node (ref "R32") (pin "1") (pinfunction "1_1") (pintype "passive"))
    )
    (net (code "59") (name "Net-(IC5-GP1)") (class "Default")
      (node (ref "IC5") (pin "11") (pinfunction "GP1_11") (pintype "bidirectional"))
      (node (ref "R31") (pin "1") (pinfunction "1_1") (pintype "passive"))
    )
    (net (code "60") (name "Net-(IC5-GP2)") (class "Default")
      (node (ref "IC5") (pin "12") (pinfunction "GP2_12") (pintype "bidirectional"))
      (node (ref "R30") (pin "1") (pinfunction "1_1") (pintype "passive"))
    )
    (net (code "61") (name "Net-(J1-GP17)") (class "Default")
      (node (ref "J1") (pin "11") (pinfunction "GP17_11") (pintype "bidirectional"))
      (node (ref "Q5") (pin "2") (pinfunction "S_2") (pintype "bidirectional"))
      (node (ref "R28") (pin "2") (pinfunction "2_2") (pintype "passive"))
    )
    (net (code "62") (name "Net-(J1-SCL)") (class "Default")
      (node (ref "J1") (pin "5") (pinfunction "SCL_5") (pintype "bidirectional"))
      (node (ref "Q4") (pin "2") (pinfunction "S_2") (pintype "bidirectional"))
      (node (ref "R26") (pin "2") (pinfunction "2_2") (pintype "passive"))
    )
    (net (code "63") (name "Net-(J1-SDA)") (class "Default")
      (node (ref "J1") (pin "3") (pinfunction "SDA_3") (pintype "bidirectional"))
      (node (ref "Q3") (pin "2") (pinfunction "S_2") (pintype "bidirectional"))
      (node (ref "R24") (pin "1") (pinfunction "1_1") (pintype "passive"))
    )
    (net (code "64") (name "Net-(LED1-BLUE)") (class "Default")
      (node (ref "LED1") (pin "4") (pinfunction "BLUE_4") (pintype "bidirectional"))
      (node (ref "R32") (pin "2") (pinfunction "2_2") (pintype "passive"))
    )
    (net (code "65") (name "Net-(LED1-GREEN)") (class "Default")
      (node (ref "LED1") (pin "3") (pinfunction "GREEN_3") (pintype "bidirectional"))
      (node (ref "R31") (pin "2") (pinfunction "2_2") (pintype "passive"))
    )
    (net (code "66") (name "Net-(LED1-RED)") (class "Default")
      (node (ref "LED1") (pin "1") (pinfunction "RED_1") (pintype "bidirectional"))
      (node (ref "R30") (pin "2") (pinfunction "2_2") (pintype "passive"))
    )
    (net (code "67") (name "Net-(M1-A2)") (class "Default")
      (node (ref "M1") (pin "J2.10") (pinfunction "A2_J2.10") (pintype "bidirectional"))
      (node (ref "R6") (pin "2") (pinfunction "WIPER_2") (pintype "bidirectional"))
    )
    (net (code "68") (name "Net-(M1-D2)") (class "Default")
      (node (ref "M1") (pin "J1.5") (pinfunction "D2_J1.5") (pintype "bidirectional"))
      (node (ref "R3") (pin "2") (pinfunction "2_2") (pintype "passive"))
    )
    (net (code "69") (name "Net-(M1-D3)") (class "Default")
      (node (ref "M1") (pin "J1.6") (pinfunction "D3_J1.6") (pintype "bidirectional"))
      (node (ref "R2") (pin "2") (pinfunction "2_2") (pintype "passive"))
    )
    (net (code "70") (name "Net-(M1-D4)") (class "Default")
      (node (ref "M1") (pin "J1.7") (pinfunction "D4_J1.7") (pintype "bidirectional"))
      (node (ref "R1") (pin "2") (pinfunction "2_2") (pintype "passive"))
    )
    (net (code "71") (name "Net-(M1-D5)") (class "Default")
      (node (ref "JP1") (pin "1") (pinfunction "1_1") (pintype "passive"))
      (node (ref "M1") (pin "J1.8") (pinfunction "D5_J1.8") (pintype "bidirectional"))
      (node (ref "R4") (pin "2") (pinfunction "2_2") (pintype "passive"))
    )
    (net (code "72") (name "Net-(Q1-G)") (class "Default")
      (node (ref "Q1") (pin "1") (pinfunction "G_1") (pintype "bidirectional"))
      (node (ref "R10") (pin "1") (pinfunction "1_1") (pintype "passive"))
    )
    (net (code "73") (name "Net-(Q2-G)") (class "Default")
      (node (ref "Q2") (pin "1") (pinfunction "G_1") (pintype "bidirectional"))
      (node (ref "R11") (pin "1") (pinfunction "1_1") (pintype "passive"))
    )
    (net (code "74") (name "Net-(U3-DELAYADJ)") (class "Default")
      (node (ref "C5") (pin "1") (pinfunction "1_1") (pintype "passive"))
      (node (ref "U3") (pin "2") (pinfunction "DELAYADJ_2") (pintype "output"))
    )
    (net (code "75") (name "Net-(U3-DUTYCYCLEADJ)") (class "Default")
      (node (ref "R8") (pin "2") (pinfunction "2_2") (pintype "passive"))
      (node (ref "U3") (pin "1") (pinfunction "DUTYCYCLEADJ_1") (pintype "input"))
    )
    (net (code "76") (name "Net-(U3-OSCFREQADJ)") (class "Default")
      (node (ref "R9") (pin "1") (pinfunction "1_1") (pintype "passive"))
      (node (ref "U3") (pin "3") (pinfunction "OSCFREQADJ_3") (pintype "input"))
    )
    (net (code "77") (name "unconnected-(IC4-DNC_1-Pad4)") (class "Default")
      (node (ref "IC4") (pin "4") (pinfunction "DNC_1_4") (pintype "bidirectional"))
    )
    (net (code "78") (name "unconnected-(IC4-DNC_2-Pad5)") (class "Default")
      (node (ref "IC4") (pin "5") (pinfunction "DNC_2_5") (pintype "bidirectional"))
    )
    (net (code "79") (name "unconnected-(IC4-NC_1-Pad3)") (class "Default")
      (node (ref "IC4") (pin "3") (pinfunction "NC_1_3") (pintype "bidirectional"))
    )
    (net (code "80") (name "unconnected-(IC4-NC_2-Pad10)") (class "Default")
      (node (ref "IC4") (pin "10") (pinfunction "NC_2_10") (pintype "bidirectional"))
    )
    (net (code "81") (name "unconnected-(IC4-NC_3-Pad11)") (class "Default")
      (node (ref "IC4") (pin "11") (pinfunction "NC_3_11") (pintype "bidirectional"))
    )
    (net (code "82") (name "unconnected-(IC5-INT-Pad8)") (class "Default")
      (node (ref "IC5") (pin "8") (pinfunction "INT_8") (pintype "input"))
    )
    (net (code "83") (name "unconnected-(IC5-NC-Pad7)") (class "Default")
      (node (ref "IC5") (pin "7") (pinfunction "NC_7") (pintype "no_connect"))
    )
    (net (code "84") (name "unconnected-(J1-GP18#-Pad12)") (class "Default")
      (node (ref "J1") (pin "12") (pinfunction "GP18#_12") (pintype "bidirectional"))
    )
    (net (code "85") (name "unconnected-(J1-GP20-Pad38)") (class "Default")
      (node (ref "J1") (pin "38") (pinfunction "GP20_38") (pintype "bidirectional"))
    )
    (net (code "86") (name "unconnected-(J1-GP21-Pad40)") (class "Default")
      (node (ref "J1") (pin "40") (pinfunction "GP21_40") (pintype "bidirectional"))
    )
    (net (code "87") (name "unconnected-(J1-GP22-Pad15)") (class "Default")
      (node (ref "J1") (pin "15") (pinfunction "GP22_15") (pintype "bidirectional"))
    )
    (net (code "88") (name "unconnected-(J1-GP23-Pad16)") (class "Default")
      (node (ref "J1") (pin "16") (pinfunction "GP23_16") (pintype "bidirectional"))
    )
    (net (code "89") (name "unconnected-(J1-GP24-Pad18)") (class "Default")
      (node (ref "J1") (pin "18") (pinfunction "GP24_18") (pintype "bidirectional"))
    )
    (net (code "90") (name "unconnected-(J1-GP25-Pad22)") (class "Default")
      (node (ref "J1") (pin "22") (pinfunction "GP25_22") (pintype "bidirectional"))
    )
    (net (code "91") (name "unconnected-(J1-GP26-Pad37)") (class "Default")
      (node (ref "J1") (pin "37") (pinfunction "GP26_37") (pintype "bidirectional"))
    )
    (net (code "92") (name "unconnected-(J1-GP27-Pad13)") (class "Default")
      (node (ref "J1") (pin "13") (pinfunction "GP27_13") (pintype "bidirectional"))
    )
    (net (code "93") (name "unconnected-(J1-ID_SC-Pad28)") (class "Default")
      (node (ref "J1") (pin "28") (pinfunction "ID_SC_28") (pintype "bidirectional"))
    )
    (net (code "94") (name "unconnected-(J1-ID_SD-Pad27)") (class "Default")
      (node (ref "J1") (pin "27") (pinfunction "ID_SD_27") (pintype "bidirectional"))
    )
    (net (code "95") (name "unconnected-(J2-Pad1)") (class "Default")
      (node (ref "J2") (pin "1") (pinfunction "1_1") (pintype "bidirectional"))
    )
    (net (code "96") (name "unconnected-(J2-Pad2)") (class "Default")
      (node (ref "J2") (pin "2") (pinfunction "2_2") (pintype "bidirectional"))
    )
    (net (code "97") (name "unconnected-(J2-Pad3)") (class "Default")
      (node (ref "J2") (pin "3") (pinfunction "3_3") (pintype "bidirectional"))
    )
    (net (code "98") (name "unconnected-(J2-Pad4)") (class "Default")
      (node (ref "J2") (pin "4") (pinfunction "4_4") (pintype "bidirectional"))
    )
    (net (code "99") (name "unconnected-(J2-Pad5)") (class "Default")
      (node (ref "J2") (pin "5") (pinfunction "5_5") (pintype "bidirectional"))
    )
    (net (code "100") (name "unconnected-(J2-Pad6)") (class "Default")
      (node (ref "J2") (pin "6") (pinfunction "6_6") (pintype "bidirectional"))
    )
    (net (code "101") (name "unconnected-(J2-Pad7)") (class "Default")
      (node (ref "J2") (pin "7") (pinfunction "7_7") (pintype "bidirectional"))
    )
    (net (code "102") (name "unconnected-(J2-Pad10)") (class "Default")
      (node (ref "J2") (pin "10") (pinfunction "10_10") (pintype "bidirectional"))
    )
    (net (code "103") (name "unconnected-(J2-Pad11)") (class "Default")
      (node (ref "J2") (pin "11") (pinfunction "11_11") (pintype "bidirectional"))
    )
    (net (code "104") (name "unconnected-(J2-Pad12)") (class "Default")
      (node (ref "J2") (pin "12") (pinfunction "12_12") (pintype "bidirectional"))
    )
    (net (code "105") (name "unconnected-(J2-Pad15)") (class "Default")
      (node (ref "J2") (pin "15") (pinfunction "15_15") (pintype "bidirectional"))
    )
    (net (code "106") (name "unconnected-(J2-Pad16)") (class "Default")
      (node (ref "J2") (pin "16") (pinfunction "16_16") (pintype "bidirectional"))
    )
    (net (code "107") (name "unconnected-(M1-A0-PadJ2.12)") (class "Default")
      (node (ref "M1") (pin "J2.12") (pinfunction "A0_J2.12") (pintype "bidirectional"))
    )
    (net (code "108") (name "unconnected-(M1-A1-PadJ2.11)") (class "Default")
      (node (ref "M1") (pin "J2.11") (pinfunction "A1_J2.11") (pintype "bidirectional"))
    )
    (net (code "109") (name "unconnected-(M1-A3-PadJ2.9)") (class "Default")
      (node (ref "M1") (pin "J2.9") (pinfunction "A3_J2.9") (pintype "bidirectional"))
    )
    (net (code "110") (name "unconnected-(M1-A4-PadJ2.8)") (class "Default")
      (node (ref "M1") (pin "J2.8") (pinfunction "A4_J2.8") (pintype "bidirectional"))
    )
    (net (code "111") (name "unconnected-(M1-A5-PadJ2.7)") (class "Default")
      (node (ref "M1") (pin "J2.7") (pinfunction "A5_J2.7") (pintype "bidirectional"))
    )
    (net (code "112") (name "unconnected-(M1-A6-PadJ2.6)") (class "Default")
      (node (ref "M1") (pin "J2.6") (pinfunction "A6_J2.6") (pintype "bidirectional"))
    )
    (net (code "113") (name "unconnected-(M1-A7-PadJ2.5)") (class "Default")
      (node (ref "M1") (pin "J2.5") (pinfunction "A7_J2.5") (pintype "bidirectional"))
    )
    (net (code "114") (name "unconnected-(M1-AREF-PadJ2.13)") (class "Default")
      (node (ref "M1") (pin "J2.13") (pinfunction "AREF_J2.13") (pintype "bidirectional"))
    )
    (net (code "115") (name "unconnected-(M1-D0{slash}RX-PadJ1.2)") (class "Default")
      (node (ref "M1") (pin "J1.2") (pinfunction "D0/RX_J1.2") (pintype "bidirectional"))
    )
    (net (code "116") (name "unconnected-(M1-D1{slash}TX-PadJ1.1)") (class "Default")
      (node (ref "M1") (pin "J1.1") (pinfunction "D1/TX_J1.1") (pintype "bidirectional"))
    )
    (net (code "117") (name "unconnected-(M1-D9-PadJ1.12)") (class "Default")
      (node (ref "M1") (pin "J1.12") (pinfunction "D9_J1.12") (pintype "bidirectional"))
    )
    (net (code "118") (name "unconnected-(M1-RST.1-PadJ1.3)") (class "Default")
      (node (ref "M1") (pin "J1.3") (pinfunction "RST.1_J1.3") (pintype "bidirectional"))
    )
    (net (code "119") (name "unconnected-(M1-RST.2-PadJ2.3)") (class "Default")
      (node (ref "M1") (pin "J2.3") (pinfunction "RST.2_J2.3") (pintype "bidirectional"))
    )
    (net (code "120") (name "unconnected-(MD$2-PadIRQ)") (class "Default")
      (node (ref "MD$2") (pin "IRQ") (pinfunction "IRQ_IRQ") (pintype "bidirectional"))
    )
    (net (code "121") (name "unconnected-(U3-STATUSOKFLAG-Pad7)") (class "Default")
      (node (ref "U3") (pin "7") (pinfunction "STATUSOKFLAG_7") (pintype "passive"))
    )
    (net (code "122") (name "unconnected-(X4-Pad3)") (class "Default")
      (node (ref "X4") (pin "3") (pinfunction "3_3") (pintype "passive"))
    )
    (net (code "123") (name "unconnected-(X4-Pad6)") (class "Default")
      (node (ref "X4") (pin "6") (pinfunction "6_6") (pintype "passive"))
    )
    (net (code "124") (name "unconnected-(X4-PadS1)") (class "Default")
      (node (ref "X4") (pin "S1") (pinfunction "S1_S1") (pintype "passive"))
    )
    (net (code "125") (name "unconnected-(X4-PadS2)") (class "Default")
      (node (ref "X4") (pin "S2") (pinfunction "S2_S2") (pintype "passive"))
    )
  )
)
